# ENGI301_PCB_design_project.net
KiCad netlist of a schematic drawn in EAGLE
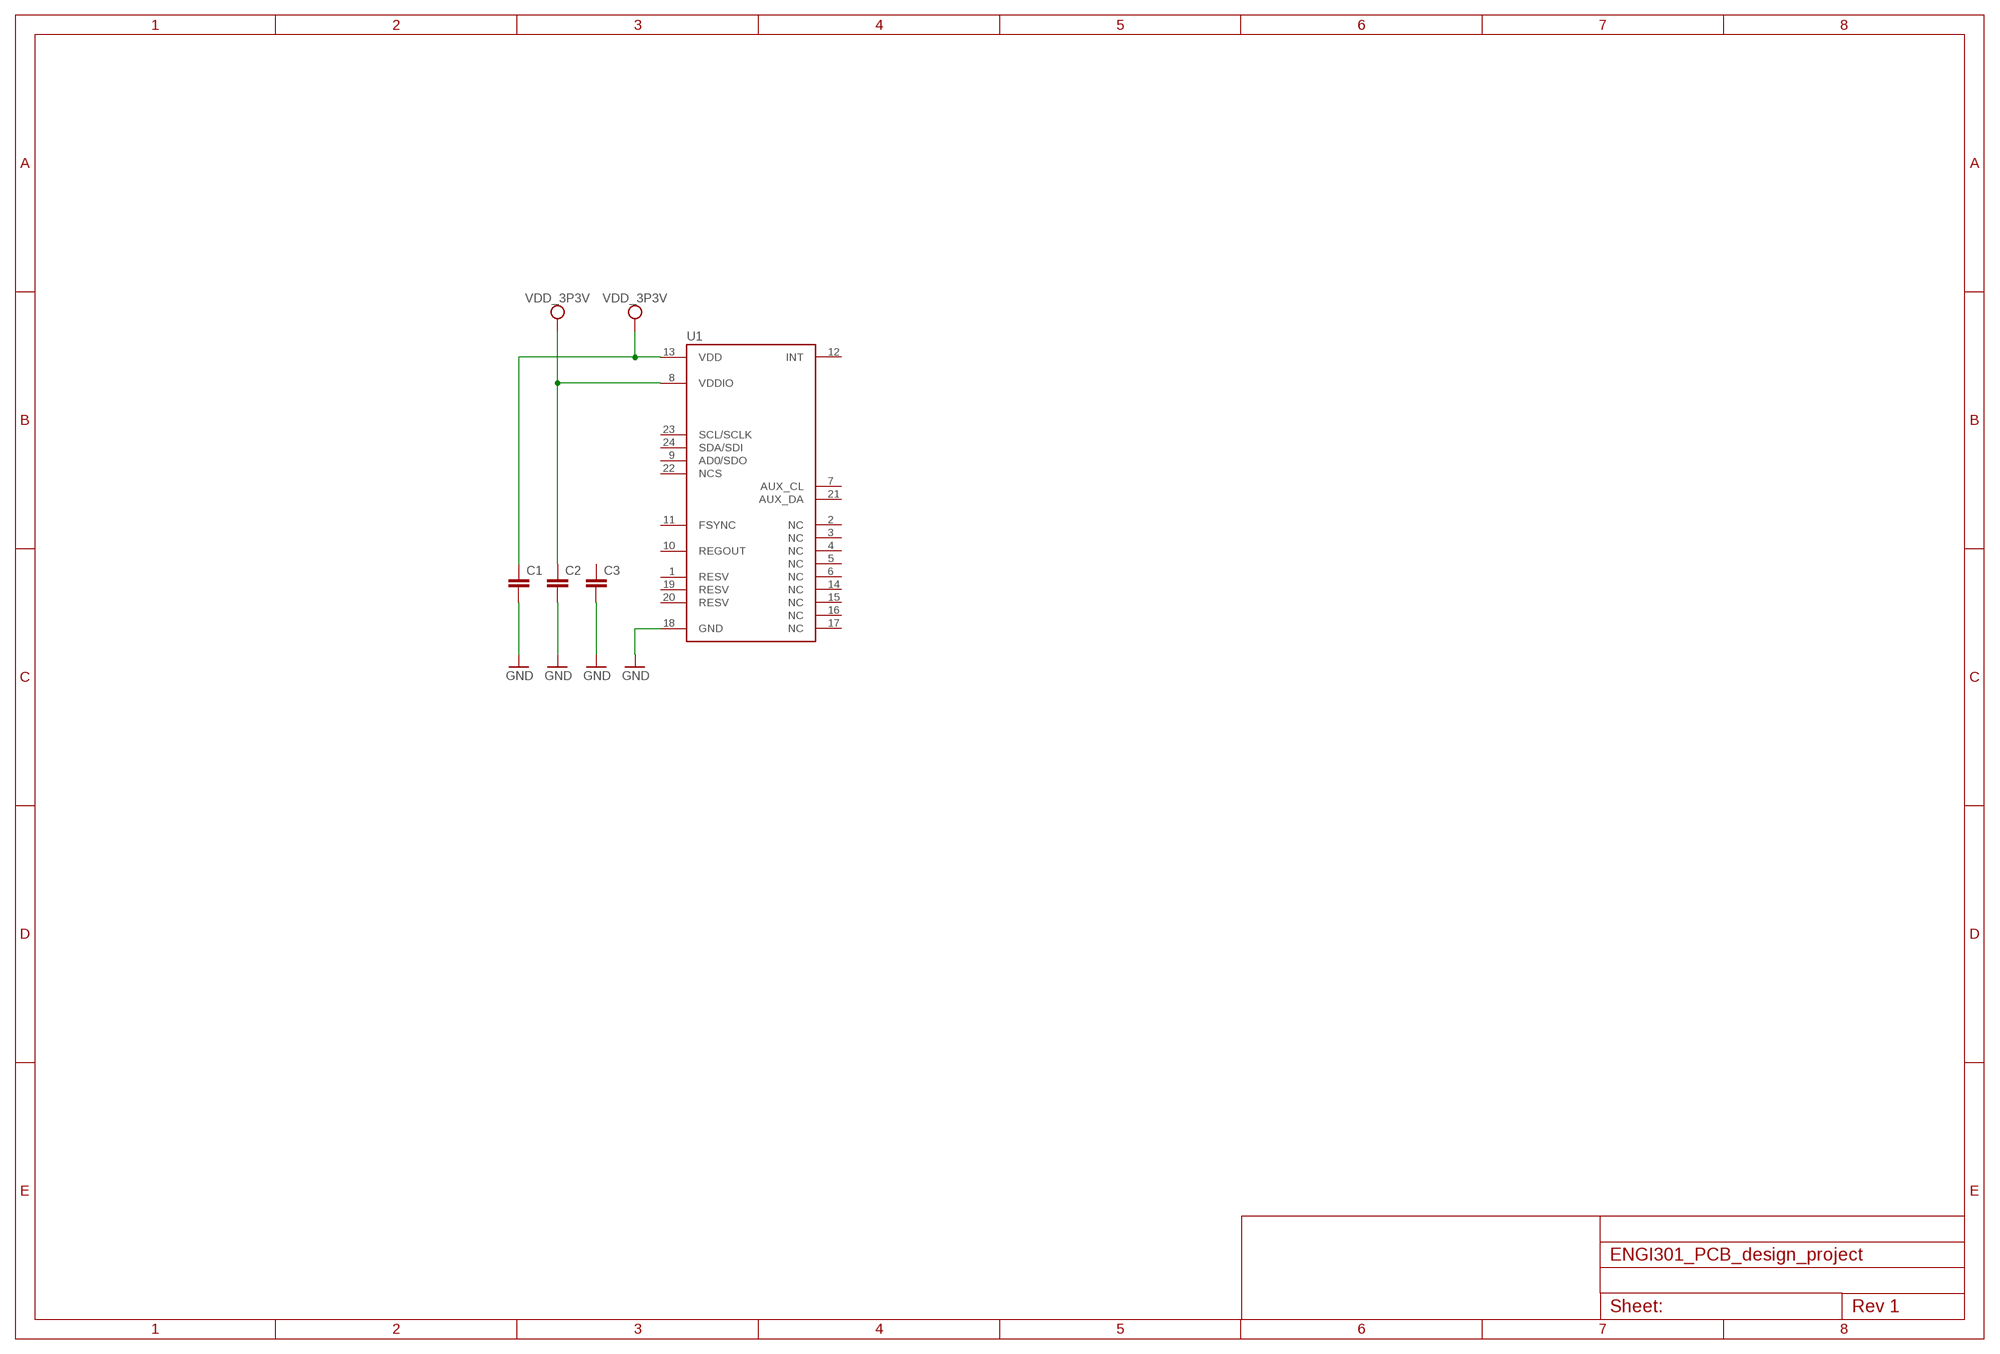
[diagram p0: schematic, sheet 1]

(export (version "E")
  (design (tool "Eeschema 10.0.6"))
  (components
    (comp (ref "C1")
      (value "C_C0402")
      (footprint "eagle-import:C0402")
      (libsource (lib "eagle-import") (part "C_C0402"))
    )
    (comp (ref "C2")
      (value "C_C0402")
      (footprint "eagle-import:C0402")
      (libsource (lib "eagle-import") (part "C_C0402"))
    )
    (comp (ref "C3")
      (value "C_C0402")
      (footprint "eagle-import:C0402")
      (libsource (lib "eagle-import") (part "C_C0402"))
    )
    (comp (ref "U1")
      (value "MPU-9250")
      (footprint "eagle-import:QFN-3MMX3MM")
      (libsource (lib "eagle-import") (part "MPU-9250"))
    )
  )
  (nets
    (net (code "1") (name "GND") (class "Default")
      (node (ref "C1") (pin "2") (pinfunction "2_2") (pintype "passive"))
      (node (ref "C2") (pin "2") (pinfunction "2_2") (pintype "passive"))
      (node (ref "C3") (pin "2") (pinfunction "2_2") (pintype "passive"))
      (node (ref "U1") (pin "18") (pinfunction "GND_18") (pintype "bidirectional"))
    )
    (net (code "2") (name "VDD_3P3V") (class "Default")
      (node (ref "C1") (pin "1") (pinfunction "1_1") (pintype "passive"))
      (node (ref "C2") (pin "1") (pinfunction "1_1") (pintype "passive"))
      (node (ref "U1") (pin "13") (pinfunction "VDD_13") (pintype "bidirectional"))
      (node (ref "U1") (pin "8") (pinfunction "VDDIO_8") (pintype "bidirectional"))
    )
    (net (code "3") (name "unconnected-(C3-Pad1)") (class "Default")
      (node (ref "C3") (pin "1") (pinfunction "1_1") (pintype "passive"))
    )
    (net (code "4") (name "unconnected-(U1-AD0{slash}SDO-Pad9)") (class "Default")
      (node (ref "U1") (pin "9") (pinfunction "AD0/SDO_9") (pintype "bidirectional"))
    )
    (net (code "5") (name "unconnected-(U1-AUX_CL-Pad7)") (class "Default")
      (node (ref "U1") (pin "7") (pinfunction "AUX_CL_7") (pintype "bidirectional"))
    )
    (net (code "6") (name "unconnected-(U1-AUX_DA-Pad21)") (class "Default")
      (node (ref "U1") (pin "21") (pinfunction "AUX_DA_21") (pintype "bidirectional"))
    )
    (net (code "7") (name "unconnected-(U1-FSYNC-Pad11)") (class "Default")
      (node (ref "U1") (pin "11") (pinfunction "FSYNC_11") (pintype "bidirectional"))
    )
    (net (code "8") (name "unconnected-(U1-INT-Pad12)") (class "Default")
      (node (ref "U1") (pin "12") (pinfunction "INT_12") (pintype "bidirectional"))
    )
    (net (code "9") (name "unconnected-(U1-NC-Pad2)") (class "Default")
      (node (ref "U1") (pin "2") (pinfunction "NC_2") (pintype "bidirectional"))
    )
    (net (code "10") (name "unconnected-(U1-NC-Pad3)") (class "Default")
      (node (ref "U1") (pin "3") (pinfunction "NC_3") (pintype "bidirectional"))
    )
    (net (code "11") (name "unconnected-(U1-NC-Pad4)") (class "Default")
      (node (ref "U1") (pin "4") (pinfunction "NC_4") (pintype "bidirectional"))
    )
    (net (code "12") (name "unconnected-(U1-NC-Pad5)") (class "Default")
      (node (ref "U1") (pin "5") (pinfunction "NC_5") (pintype "bidirectional"))
    )
    (net (code "13") (name "unconnected-(U1-NC-Pad6)") (class "Default")
      (node (ref "U1") (pin "6") (pinfunction "NC_6") (pintype "bidirectional"))
    )
    (net (code "14") (name "unconnected-(U1-NC-Pad14)") (class "Default")
      (node (ref "U1") (pin "14") (pinfunction "NC_14") (pintype "bidirectional"))
    )
    (net (code "15") (name "unconnected-(U1-NC-Pad15)") (class "Default")
      (node (ref "U1") (pin "15") (pinfunction "NC_15") (pintype "bidirectional"))
    )
    (net (code "16") (name "unconnected-(U1-NC-Pad16)") (class "Default")
      (node (ref "U1") (pin "16") (pinfunction "NC_16") (pintype "bidirectional"))
    )
    (net (code "17") (name "unconnected-(U1-NC-Pad17)") (class "Default")
      (node (ref "U1") (pin "17") (pinfunction "NC_17") (pintype "bidirectional"))
    )
    (net (code "18") (name "unconnected-(U1-NCS-Pad22)") (class "Default")
      (node (ref "U1") (pin "22") (pinfunction "NCS_22") (pintype "bidirectional"))
    )
    (net (code "19") (name "unconnected-(U1-REGOUT-Pad10)") (class "Default")
      (node (ref "U1") (pin "10") (pinfunction "REGOUT_10") (pintype "bidirectional"))
    )
    (net (code "20") (name "unconnected-(U1-RESV-Pad1)") (class "Default")
      (node (ref "U1") (pin "1") (pinfunction "RESV_1") (pintype "bidirectional"))
    )
    (net (code "21") (name "unconnected-(U1-RESV-Pad19)") (class "Default")
      (node (ref "U1") (pin "19") (pinfunction "RESV_19") (pintype "bidirectional"))
    )
    (net (code "22") (name "unconnected-(U1-RESV-Pad20)") (class "Default")
      (node (ref "U1") (pin "20") (pinfunction "RESV_20") (pintype "bidirectional"))
    )
    (net (code "23") (name "unconnected-(U1-SCL{slash}SCLK-Pad23)") (class "Default")
      (node (ref "U1") (pin "23") (pinfunction "SCL/SCLK_23") (pintype "bidirectional"))
    )
    (net (code "24") (name "unconnected-(U1-SDA{slash}SDI-Pad24)") (class "Default")
      (node (ref "U1") (pin "24") (pinfunction "SDA/SDI_24") (pintype "bidirectional"))
    )
  )
)
